# DS1307.net
KiCad netlist of a schematic drawn in Altium Designer
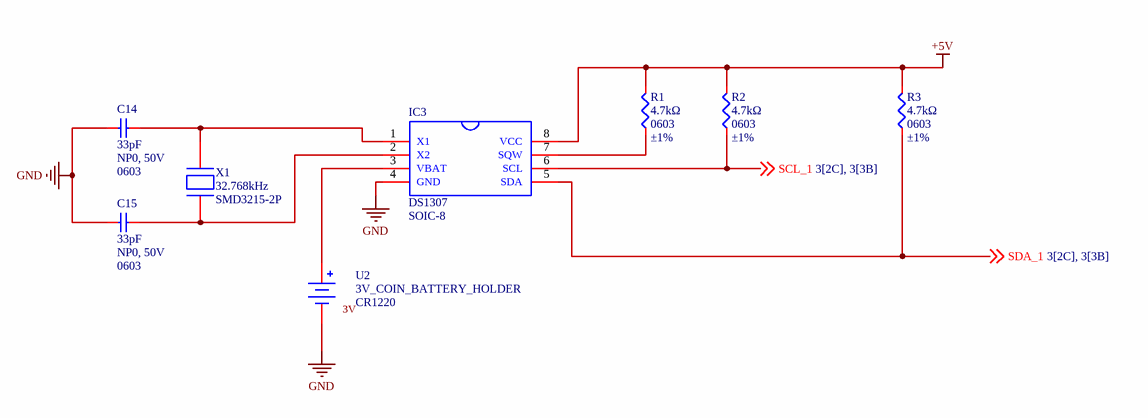
[diagram p0: DS1307.SchDoc]

(export (version "E")
  (design (tool "Eeschema 10.0.6"))
  (components
    (comp (ref "C14")
      (value "33pF")
      (footprint "C0603")
      (description "50V 33pF NP0 ±5% 0603 Multilayer Ceramic Capacitors MLCC - SMD/SMT ROHS")
      (fields
        (field (name "MANUFACTURER") "YAGEO")
        (field (name "MFR. PART") "CC0603JRNPO9BN330")
        (field (name "TEMPERATURE COEFFICIENT") "NP0, 50V")
        (field (name "PACKAGE") "0603")
      )
      (libsource (lib "Capacitor") (part "C0603_MLCC_33pF_NP0_50V"))
    )
    (comp (ref "C15")
      (value "33pF")
      (footprint "C0603")
      (description "50V 33pF NP0 ±5% 0603 Multilayer Ceramic Capacitors MLCC - SMD/SMT ROHS")
      (fields
        (field (name "MANUFACTURER") "YAGEO")
        (field (name "MFR. PART") "CC0603JRNPO9BN330")
        (field (name "TEMPERATURE COEFFICIENT") "NP0, 50V")
        (field (name "PACKAGE") "0603")
      )
      (libsource (lib "Capacitor") (part "C0603_MLCC_33pF_NP0_50V"))
    )
    (comp (ref "IC3")
      (value "DS1307")
      (footprint "SOIC-8")
      (description "I2C SOIC-8 Real Time Clocks ROHS")
      (fields
        (field (name "MANUFACTURER") "MAXIM")
        (field (name "MFR. PART") "DS1307Z+T&R")
        (field (name "PACKAGE") "SOIC-8")
      )
      (libsource (lib "IC") (part "DS1307-SOIC8"))
    )
    (comp (ref "R1")
      (value "4.7kΩ")
      (footprint "R0603")
      (description "100mW Thick Film Resistor 75V ±100ppm/℃ ±1% 4.7kΩ 0603 Chip Resistor - Surface Mount ROHS")
      (fields
        (field (name "MANUFACTURER") "YAGEO")
        (field (name "MFR. PART") "RC0603FR-074K7L")
        (field (name "PACKAGE") "0603")
        (field (name "TOLERANCE") "±1%")
      )
      (libsource (lib "Resistor") (part "R0603_4.7kΩ_±1%"))
    )
    (comp (ref "R2")
      (value "4.7kΩ")
      (footprint "R0603")
      (description "100mW Thick Film Resistor 75V ±100ppm/℃ ±1% 4.7kΩ 0603 Chip Resistor - Surface Mount ROHS")
      (fields
        (field (name "MANUFACTURER") "YAGEO")
        (field (name "MFR. PART") "RC0603FR-074K7L")
        (field (name "PACKAGE") "0603")
        (field (name "TOLERANCE") "±1%")
      )
      (libsource (lib "Resistor") (part "R0603_4.7kΩ_±1%"))
    )
    (comp (ref "R3")
      (value "4.7kΩ")
      (footprint "R0603")
      (description "100mW Thick Film Resistor 75V ±100ppm/℃ ±1% 4.7kΩ 0603 Chip Resistor - Surface Mount ROHS")
      (fields
        (field (name "MANUFACTURER") "YAGEO")
        (field (name "MFR. PART") "RC0603FR-074K7L")
        (field (name "PACKAGE") "0603")
        (field (name "TOLERANCE") "±1%")
      )
      (libsource (lib "Resistor") (part "R0603_4.7kΩ_±1%"))
    )
    (comp (ref "U2")
      (value "3V_COIN_BATTERY_HOLDER")
      (footprint "3V_COIN_BATERRY_HOLDER_CR1220")
      (description "Battery Holder -25℃~+85℃ Phosphor Bronze CR1220 SMD Button And Strip Battery Connector ROHS")
      (fields
        (field (name "MANUFACTURER") "MYOUNG")
        (field (name "LCSC PART") "C964723")
        (field (name "BATTERY TYPE") "CR1220")
      )
      (libsource (lib "PIN") (part "3V_COIN_BATTERY_HOLDER"))
    )
    (comp (ref "X1")
      (value "32.768kHz")
      (footprint "SMD3215-2P")
      (description "32.768kHz 12.5pF ±20ppm SMD3215-2P Crystals ROHS")
      (fields
        (field (name "MANUFACTURER") "NDK")
        (field (name "MFR. PART") "NX3215SA-32.768K-STD-MUA-8")
        (field (name "PACKAGE") "SMD3215-2P")
      )
      (libsource (lib "CRYSTAL") (part "Crystal_32.768Khz"))
    )
  )
  (nets
    (net (code "1") (name "+5V") (class "Default")
      (node (ref "IC3") (pin "8") (pinfunction "VCC_8") (pintype "passive"))
      (node (ref "R1") (pin "2") (pinfunction "2_2") (pintype "passive"))
      (node (ref "R2") (pin "2") (pinfunction "2_2") (pintype "passive"))
      (node (ref "R3") (pin "2") (pinfunction "2_2") (pintype "passive"))
    )
    (net (code "2") (name "GND") (class "Default")
      (node (ref "C14") (pin "2") (pinfunction "2_2") (pintype "passive"))
      (node (ref "C15") (pin "2") (pinfunction "2_2") (pintype "passive"))
      (node (ref "IC3") (pin "4") (pinfunction "GND_4") (pintype "passive"))
      (node (ref "U2") (pin "2") (pinfunction "2_2") (pintype "passive"))
    )
    (net (code "3") (name "Net-(IC3-SQW)") (class "Default")
      (node (ref "IC3") (pin "7") (pinfunction "SQW_7") (pintype "passive"))
      (node (ref "R1") (pin "1") (pinfunction "1_1") (pintype "passive"))
    )
    (net (code "4") (name "Net-(IC3-VBAT)") (class "Default")
      (node (ref "IC3") (pin "3") (pinfunction "VBAT_3") (pintype "passive"))
      (node (ref "U2") (pin "1") (pinfunction "1_1") (pintype "passive"))
    )
    (net (code "5") (name "Net-(IC3-X1)") (class "Default")
      (node (ref "C14") (pin "1") (pinfunction "1_1") (pintype "passive"))
      (node (ref "IC3") (pin "1") (pinfunction "X1_1") (pintype "passive"))
      (node (ref "X1") (pin "2") (pinfunction "2_2") (pintype "passive"))
    )
    (net (code "6") (name "Net-(IC3-X2)") (class "Default")
      (node (ref "C15") (pin "1") (pinfunction "1_1") (pintype "passive"))
      (node (ref "IC3") (pin "2") (pinfunction "X2_2") (pintype "passive"))
      (node (ref "X1") (pin "1") (pinfunction "1_1") (pintype "passive"))
    )
    (net (code "7") (name "SCL_1") (class "Default")
      (node (ref "IC3") (pin "6") (pinfunction "SCL_6") (pintype "passive"))
      (node (ref "R2") (pin "1") (pinfunction "1_1") (pintype "passive"))
    )
    (net (code "8") (name "SDA_1") (class "Default")
      (node (ref "IC3") (pin "5") (pinfunction "SDA_5") (pintype "passive"))
      (node (ref "R3") (pin "1") (pinfunction "1_1") (pintype "passive"))
    )
  )
)
